# Breakout.net
KiCad netlist of a schematic drawn in EAGLE
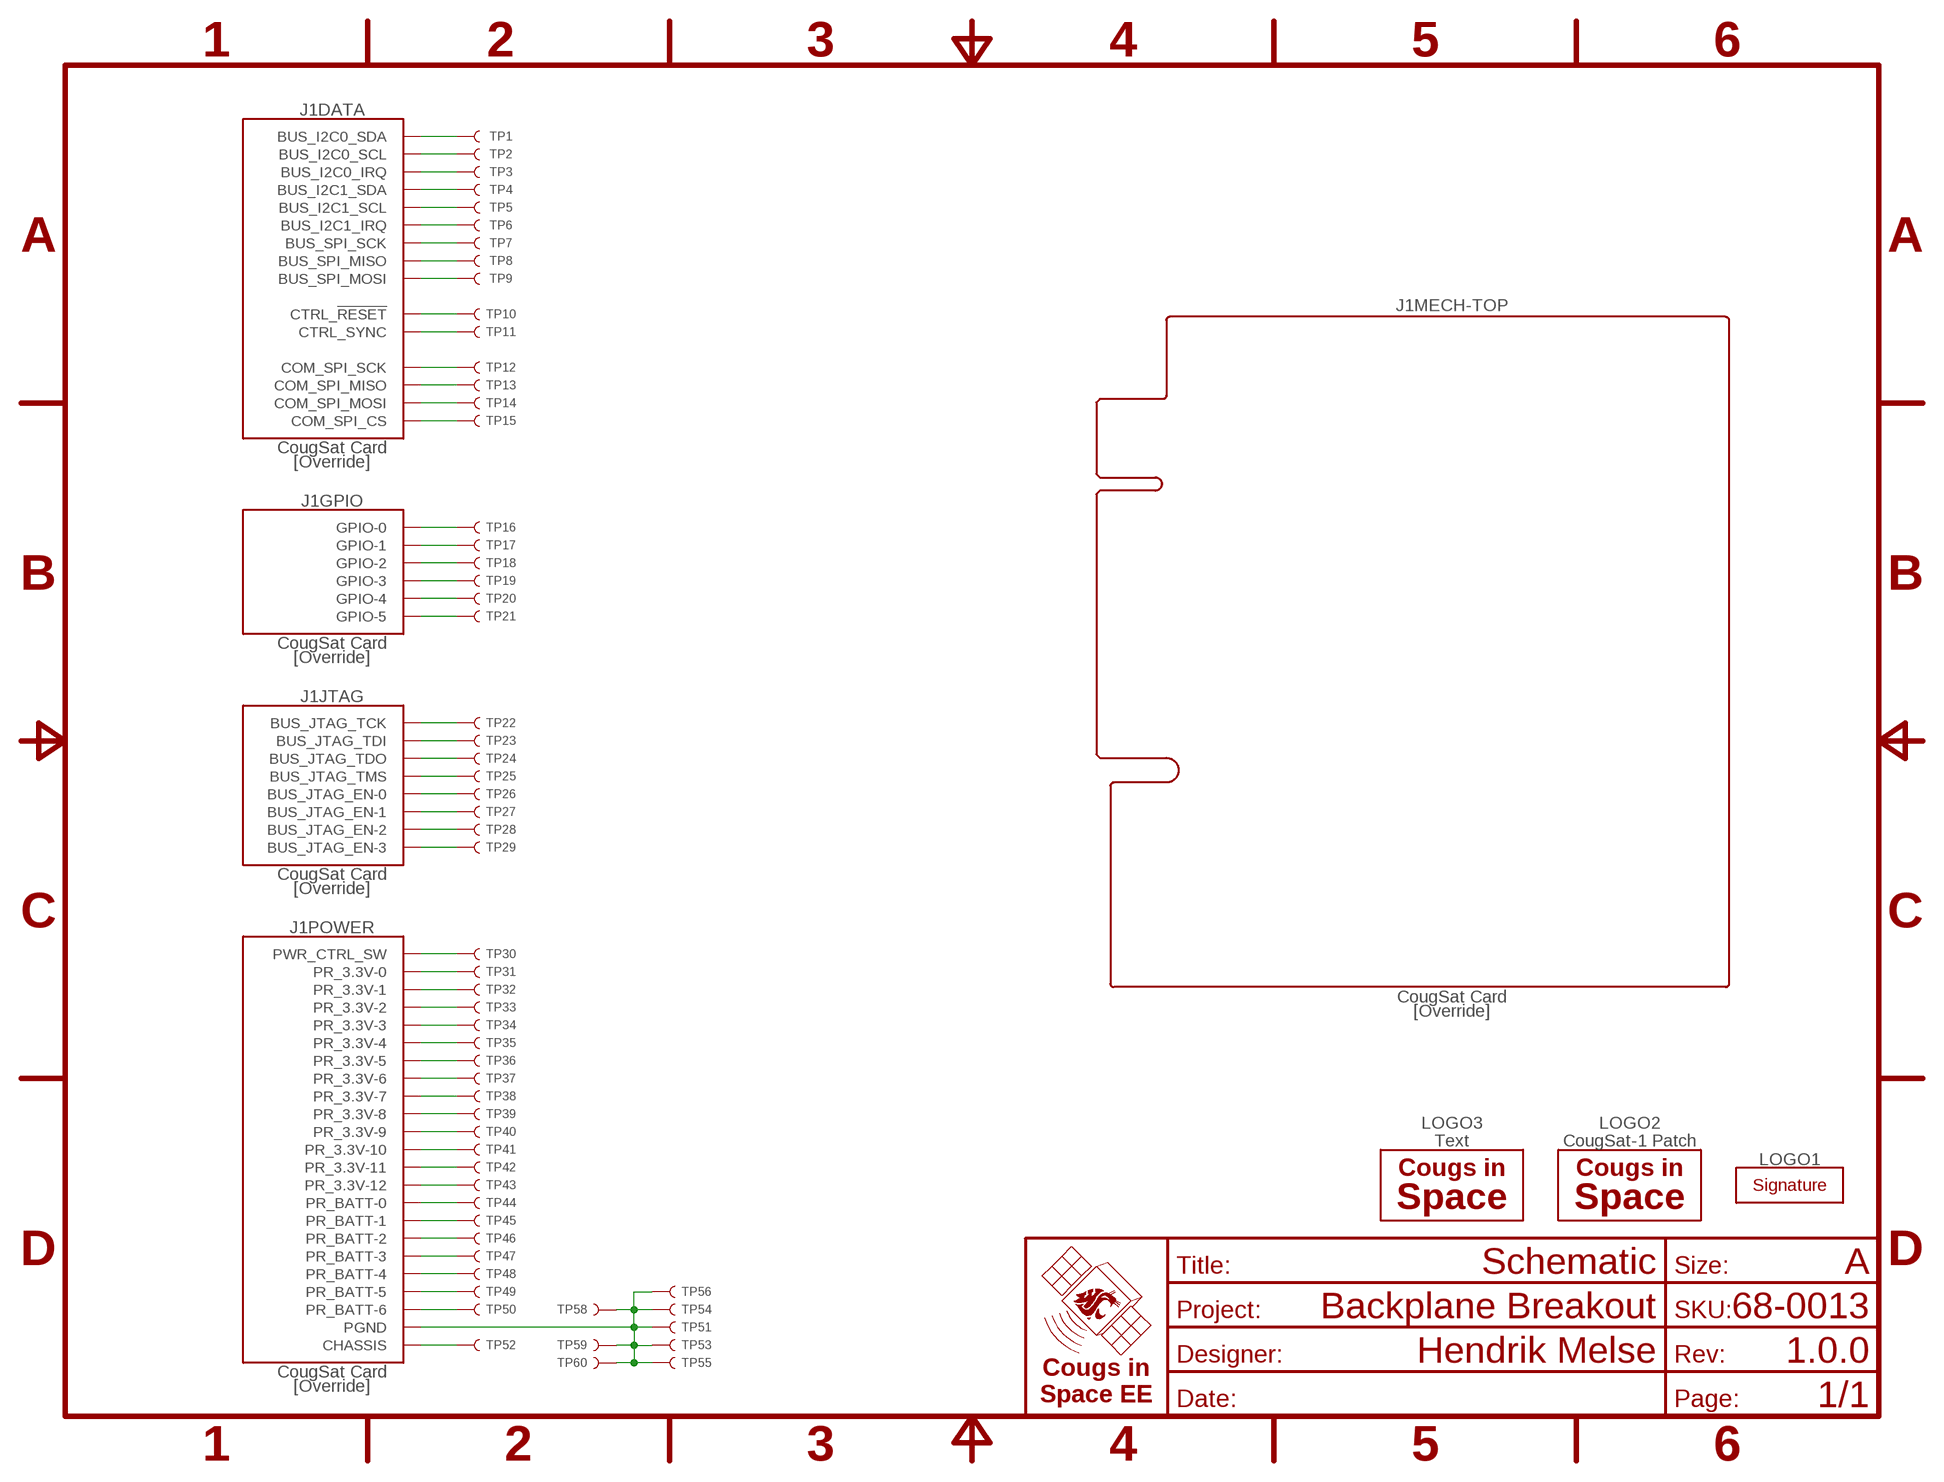
[diagram p0: schematic, sheet 1]

(export (version "E")
  (design (tool "Eeschema 10.0.6"))
  (components
    (comp (ref "J1")
      (value "CougSat Card")
      (footprint "eagle-import:CARD-FULL")
      (libsource (lib "eagle-import") (part "CIS_CARD"))
    )
    (comp (ref "LOGO1")
      (value "SIGNATUREHENDRIK")
      (footprint "eagle-import:SIGN-HENDRIK")
      (libsource (lib "eagle-import") (part "SIGNATUREHENDRIK"))
    )
    (comp (ref "LOGO2")
      (value "CougSat-1 Patch")
      (footprint "eagle-import:CIS-PATCH-1")
      (libsource (lib "eagle-import") (part "CIS-LOGO-PATCH-1"))
    )
    (comp (ref "LOGO3")
      (value "Text")
      (footprint "eagle-import:CIS-TEXT")
      (libsource (lib "eagle-import") (part "CIS-LOGO-TEXT"))
    )
    (comp (ref "TP1")
      (value "TEST_POINT-THT-1.0")
      (footprint "eagle-import:THT-1.0")
      (libsource (lib "eagle-import") (part "TEST_POINT-THT-1.0"))
    )
    (comp (ref "TP2")
      (value "TEST_POINT-THT-1.0")
      (footprint "eagle-import:THT-1.0")
      (libsource (lib "eagle-import") (part "TEST_POINT-THT-1.0"))
    )
    (comp (ref "TP3")
      (value "TEST_POINT-THT-1.0")
      (footprint "eagle-import:THT-1.0")
      (libsource (lib "eagle-import") (part "TEST_POINT-THT-1.0"))
    )
    (comp (ref "TP4")
      (value "TEST_POINT-THT-1.0")
      (footprint "eagle-import:THT-1.0")
      (libsource (lib "eagle-import") (part "TEST_POINT-THT-1.0"))
    )
    (comp (ref "TP5")
      (value "TEST_POINT-THT-1.0")
      (footprint "eagle-import:THT-1.0")
      (libsource (lib "eagle-import") (part "TEST_POINT-THT-1.0"))
    )
    (comp (ref "TP6")
      (value "TEST_POINT-THT-1.0")
      (footprint "eagle-import:THT-1.0")
      (libsource (lib "eagle-import") (part "TEST_POINT-THT-1.0"))
    )
    (comp (ref "TP7")
      (value "TEST_POINT-THT-1.0")
      (footprint "eagle-import:THT-1.0")
      (libsource (lib "eagle-import") (part "TEST_POINT-THT-1.0"))
    )
    (comp (ref "TP8")
      (value "TEST_POINT-THT-1.0")
      (footprint "eagle-import:THT-1.0")
      (libsource (lib "eagle-import") (part "TEST_POINT-THT-1.0"))
    )
    (comp (ref "TP9")
      (value "TEST_POINT-THT-1.0")
      (footprint "eagle-import:THT-1.0")
      (libsource (lib "eagle-import") (part "TEST_POINT-THT-1.0"))
    )
    (comp (ref "TP10")
      (value "TEST_POINT-THT-1.0")
      (footprint "eagle-import:THT-1.0")
      (libsource (lib "eagle-import") (part "TEST_POINT-THT-1.0"))
    )
    (comp (ref "TP11")
      (value "TEST_POINT-THT-1.0")
      (footprint "eagle-import:THT-1.0")
      (libsource (lib "eagle-import") (part "TEST_POINT-THT-1.0"))
    )
    (comp (ref "TP12")
      (value "TEST_POINT-THT-1.0")
      (footprint "eagle-import:THT-1.0")
      (libsource (lib "eagle-import") (part "TEST_POINT-THT-1.0"))
    )
    (comp (ref "TP13")
      (value "TEST_POINT-THT-1.0")
      (footprint "eagle-import:THT-1.0")
      (libsource (lib "eagle-import") (part "TEST_POINT-THT-1.0"))
    )
    (comp (ref "TP14")
      (value "TEST_POINT-THT-1.0")
      (footprint "eagle-import:THT-1.0")
      (libsource (lib "eagle-import") (part "TEST_POINT-THT-1.0"))
    )
    (comp (ref "TP15")
      (value "TEST_POINT-THT-1.0")
      (footprint "eagle-import:THT-1.0")
      (libsource (lib "eagle-import") (part "TEST_POINT-THT-1.0"))
    )
    (comp (ref "TP16")
      (value "TEST_POINT-THT-1.0")
      (footprint "eagle-import:THT-1.0")
      (libsource (lib "eagle-import") (part "TEST_POINT-THT-1.0"))
    )
    (comp (ref "TP17")
      (value "TEST_POINT-THT-1.0")
      (footprint "eagle-import:THT-1.0")
      (libsource (lib "eagle-import") (part "TEST_POINT-THT-1.0"))
    )
    (comp (ref "TP18")
      (value "TEST_POINT-THT-1.0")
      (footprint "eagle-import:THT-1.0")
      (libsource (lib "eagle-import") (part "TEST_POINT-THT-1.0"))
    )
    (comp (ref "TP19")
      (value "TEST_POINT-THT-1.0")
      (footprint "eagle-import:THT-1.0")
      (libsource (lib "eagle-import") (part "TEST_POINT-THT-1.0"))
    )
    (comp (ref "TP20")
      (value "TEST_POINT-THT-1.0")
      (footprint "eagle-import:THT-1.0")
      (libsource (lib "eagle-import") (part "TEST_POINT-THT-1.0"))
    )
    (comp (ref "TP21")
      (value "TEST_POINT-THT-1.0")
      (footprint "eagle-import:THT-1.0")
      (libsource (lib "eagle-import") (part "TEST_POINT-THT-1.0"))
    )
    (comp (ref "TP22")
      (value "TEST_POINT-THT-1.0")
      (footprint "eagle-import:THT-1.0")
      (libsource (lib "eagle-import") (part "TEST_POINT-THT-1.0"))
    )
    (comp (ref "TP23")
      (value "TEST_POINT-THT-1.0")
      (footprint "eagle-import:THT-1.0")
      (libsource (lib "eagle-import") (part "TEST_POINT-THT-1.0"))
    )
    (comp (ref "TP24")
      (value "TEST_POINT-THT-1.0")
      (footprint "eagle-import:THT-1.0")
      (libsource (lib "eagle-import") (part "TEST_POINT-THT-1.0"))
    )
    (comp (ref "TP25")
      (value "TEST_POINT-THT-1.0")
      (footprint "eagle-import:THT-1.0")
      (libsource (lib "eagle-import") (part "TEST_POINT-THT-1.0"))
    )
    (comp (ref "TP26")
      (value "TEST_POINT-THT-1.0")
      (footprint "eagle-import:THT-1.0")
      (libsource (lib "eagle-import") (part "TEST_POINT-THT-1.0"))
    )
    (comp (ref "TP27")
      (value "TEST_POINT-THT-1.0")
      (footprint "eagle-import:THT-1.0")
      (libsource (lib "eagle-import") (part "TEST_POINT-THT-1.0"))
    )
    (comp (ref "TP28")
      (value "TEST_POINT-THT-1.0")
      (footprint "eagle-import:THT-1.0")
      (libsource (lib "eagle-import") (part "TEST_POINT-THT-1.0"))
    )
    (comp (ref "TP29")
      (value "TEST_POINT-THT-1.0")
      (footprint "eagle-import:THT-1.0")
      (libsource (lib "eagle-import") (part "TEST_POINT-THT-1.0"))
    )
    (comp (ref "TP30")
      (value "TEST_POINT-THT-1.0")
      (footprint "eagle-import:THT-1.0")
      (libsource (lib "eagle-import") (part "TEST_POINT-THT-1.0"))
    )
    (comp (ref "TP31")
      (value "TEST_POINT-THT-1.0")
      (footprint "eagle-import:THT-1.0")
      (libsource (lib "eagle-import") (part "TEST_POINT-THT-1.0"))
    )
    (comp (ref "TP32")
      (value "TEST_POINT-THT-1.0")
      (footprint "eagle-import:THT-1.0")
      (libsource (lib "eagle-import") (part "TEST_POINT-THT-1.0"))
    )
    (comp (ref "TP33")
      (value "TEST_POINT-THT-1.0")
      (footprint "eagle-import:THT-1.0")
      (libsource (lib "eagle-import") (part "TEST_POINT-THT-1.0"))
    )
    (comp (ref "TP34")
      (value "TEST_POINT-THT-1.0")
      (footprint "eagle-import:THT-1.0")
      (libsource (lib "eagle-import") (part "TEST_POINT-THT-1.0"))
    )
    (comp (ref "TP35")
      (value "TEST_POINT-THT-1.0")
      (footprint "eagle-import:THT-1.0")
      (libsource (lib "eagle-import") (part "TEST_POINT-THT-1.0"))
    )
    (comp (ref "TP36")
      (value "TEST_POINT-THT-1.0")
      (footprint "eagle-import:THT-1.0")
      (libsource (lib "eagle-import") (part "TEST_POINT-THT-1.0"))
    )
    (comp (ref "TP37")
      (value "TEST_POINT-THT-1.0")
      (footprint "eagle-import:THT-1.0")
      (libsource (lib "eagle-import") (part "TEST_POINT-THT-1.0"))
    )
    (comp (ref "TP38")
      (value "TEST_POINT-THT-1.0")
      (footprint "eagle-import:THT-1.0")
      (libsource (lib "eagle-import") (part "TEST_POINT-THT-1.0"))
    )
    (comp (ref "TP39")
      (value "TEST_POINT-THT-1.0")
      (footprint "eagle-import:THT-1.0")
      (libsource (lib "eagle-import") (part "TEST_POINT-THT-1.0"))
    )
    (comp (ref "TP40")
      (value "TEST_POINT-THT-1.0")
      (footprint "eagle-import:THT-1.0")
      (libsource (lib "eagle-import") (part "TEST_POINT-THT-1.0"))
    )
    (comp (ref "TP41")
      (value "TEST_POINT-THT-1.0")
      (footprint "eagle-import:THT-1.0")
      (libsource (lib "eagle-import") (part "TEST_POINT-THT-1.0"))
    )
    (comp (ref "TP42")
      (value "TEST_POINT-THT-1.0")
      (footprint "eagle-import:THT-1.0")
      (libsource (lib "eagle-import") (part "TEST_POINT-THT-1.0"))
    )
    (comp (ref "TP43")
      (value "TEST_POINT-THT-1.0")
      (footprint "eagle-import:THT-1.0")
      (libsource (lib "eagle-import") (part "TEST_POINT-THT-1.0"))
    )
    (comp (ref "TP44")
      (value "TEST_POINT-THT-1.0")
      (footprint "eagle-import:THT-1.0")
      (libsource (lib "eagle-import") (part "TEST_POINT-THT-1.0"))
    )
    (comp (ref "TP45")
      (value "TEST_POINT-THT-1.0")
      (footprint "eagle-import:THT-1.0")
      (libsource (lib "eagle-import") (part "TEST_POINT-THT-1.0"))
    )
    (comp (ref "TP46")
      (value "TEST_POINT-THT-1.0")
      (footprint "eagle-import:THT-1.0")
      (libsource (lib "eagle-import") (part "TEST_POINT-THT-1.0"))
    )
    (comp (ref "TP47")
      (value "TEST_POINT-THT-1.0")
      (footprint "eagle-import:THT-1.0")
      (libsource (lib "eagle-import") (part "TEST_POINT-THT-1.0"))
    )
    (comp (ref "TP48")
      (value "TEST_POINT-THT-1.0")
      (footprint "eagle-import:THT-1.0")
      (libsource (lib "eagle-import") (part "TEST_POINT-THT-1.0"))
    )
    (comp (ref "TP49")
      (value "TEST_POINT-THT-1.0")
      (footprint "eagle-import:THT-1.0")
      (libsource (lib "eagle-import") (part "TEST_POINT-THT-1.0"))
    )
    (comp (ref "TP50")
      (value "TEST_POINT-THT-1.0")
      (footprint "eagle-import:THT-1.0")
      (libsource (lib "eagle-import") (part "TEST_POINT-THT-1.0"))
    )
    (comp (ref "TP51")
      (value "TEST_POINT-THT-1.0")
      (footprint "eagle-import:THT-1.0")
      (libsource (lib "eagle-import") (part "TEST_POINT-THT-1.0"))
    )
    (comp (ref "TP52")
      (value "TEST_POINT-THT-1.0")
      (footprint "eagle-import:THT-1.0")
      (libsource (lib "eagle-import") (part "TEST_POINT-THT-1.0"))
    )
    (comp (ref "TP53")
      (value "TEST_POINT-THT-1.0")
      (footprint "eagle-import:THT-1.0")
      (libsource (lib "eagle-import") (part "TEST_POINT-THT-1.0"))
    )
    (comp (ref "TP54")
      (value "TEST_POINT-THT-1.0")
      (footprint "eagle-import:THT-1.0")
      (libsource (lib "eagle-import") (part "TEST_POINT-THT-1.0"))
    )
    (comp (ref "TP55")
      (value "TEST_POINT-THT-1.0")
      (footprint "eagle-import:THT-1.0")
      (libsource (lib "eagle-import") (part "TEST_POINT-THT-1.0"))
    )
    (comp (ref "TP56")
      (value "TEST_POINT-THT-1.0")
      (footprint "eagle-import:THT-1.0")
      (libsource (lib "eagle-import") (part "TEST_POINT-THT-1.0"))
    )
    (comp (ref "TP58")
      (value "TEST_POINT-THT-1.0")
      (footprint "eagle-import:THT-1.0")
      (libsource (lib "eagle-import") (part "TEST_POINT-THT-1.0"))
    )
    (comp (ref "TP59")
      (value "TEST_POINT-THT-1.0")
      (footprint "eagle-import:THT-1.0")
      (libsource (lib "eagle-import") (part "TEST_POINT-THT-1.0"))
    )
    (comp (ref "TP60")
      (value "TEST_POINT-THT-1.0")
      (footprint "eagle-import:THT-1.0")
      (libsource (lib "eagle-import") (part "TEST_POINT-THT-1.0"))
    )
  )
  (nets
    (net (code "1") (name "/CHASSIS") (class "Default")
      (node (ref "J1") (pin "CHASSIS@1") (pinfunction "CHASSIS_CHASSIS@1") (pintype "power_in"))
      (node (ref "J1") (pin "CHASSIS@2") (pinfunction "CHASSIS_CHASSIS@2") (pintype "power_in"))
      (node (ref "J1") (pin "CHASSIS@3") (pinfunction "CHASSIS_CHASSIS@3") (pintype "power_in"))
      (node (ref "J1") (pin "CHASSIS@4") (pinfunction "CHASSIS_CHASSIS@4") (pintype "power_in"))
      (node (ref "TP52") (pin "1") (pinfunction "1_1") (pintype "passive"))
    )
    (net (code "2") (name "/PGND") (class "Default")
      (node (ref "J1") (pin "A21") (pinfunction "PGND_A21") (pintype "power_in"))
      (node (ref "J1") (pin "A22") (pinfunction "PGND_A22") (pintype "power_in"))
      (node (ref "J1") (pin "A23") (pinfunction "PGND_A23") (pintype "power_in"))
      (node (ref "J1") (pin "B21") (pinfunction "PGND_B21") (pintype "power_in"))
      (node (ref "J1") (pin "B22") (pinfunction "PGND_B22") (pintype "power_in"))
      (node (ref "J1") (pin "B23") (pinfunction "PGND_B23") (pintype "power_in"))
      (node (ref "J1") (pin "B24") (pinfunction "PGND_B24") (pintype "power_in"))
      (node (ref "J1") (pin "B25") (pinfunction "PGND_B25") (pintype "power_in"))
      (node (ref "J1") (pin "B26") (pinfunction "PGND_B26") (pintype "power_in"))
      (node (ref "J1") (pin "B27") (pinfunction "PGND_B27") (pintype "power_in"))
      (node (ref "J1") (pin "B28") (pinfunction "PGND_B28") (pintype "power_in"))
      (node (ref "J1") (pin "B29") (pinfunction "PGND_B29") (pintype "power_in"))
      (node (ref "TP51") (pin "1") (pinfunction "1_1") (pintype "passive"))
      (node (ref "TP53") (pin "1") (pinfunction "1_1") (pintype "passive"))
      (node (ref "TP54") (pin "1") (pinfunction "1_1") (pintype "passive"))
      (node (ref "TP55") (pin "1") (pinfunction "1_1") (pintype "passive"))
      (node (ref "TP56") (pin "1") (pinfunction "1_1") (pintype "passive"))
      (node (ref "TP58") (pin "1") (pinfunction "1_1") (pintype "passive"))
      (node (ref "TP59") (pin "1") (pinfunction "1_1") (pintype "passive"))
      (node (ref "TP60") (pin "1") (pinfunction "1_1") (pintype "passive"))
    )
    (net (code "3") (name "/PR_3.3V-0") (class "Default")
      (node (ref "J1") (pin "A1") (pinfunction "PR_3.3V-0_A1") (pintype "power_in"))
      (node (ref "J1") (pin "B1") (pinfunction "PR_3.3V-0_B1") (pintype "power_in"))
      (node (ref "TP31") (pin "1") (pinfunction "1_1") (pintype "passive"))
    )
    (net (code "4") (name "/PR_3.3V-1") (class "Default")
      (node (ref "J1") (pin "A2") (pinfunction "PR_3.3V-1_A2") (pintype "power_in"))
      (node (ref "J1") (pin "B2") (pinfunction "PR_3.3V-1_B2") (pintype "power_in"))
      (node (ref "TP32") (pin "1") (pinfunction "1_1") (pintype "passive"))
    )
    (net (code "5") (name "/PR_3.3V-2") (class "Default")
      (node (ref "J1") (pin "A3") (pinfunction "PR_3.3V-2_A3") (pintype "power_in"))
      (node (ref "J1") (pin "B3") (pinfunction "PR_3.3V-2_B3") (pintype "power_in"))
      (node (ref "TP33") (pin "1") (pinfunction "1_1") (pintype "passive"))
    )
    (net (code "6") (name "/PR_3.3V-3") (class "Default")
      (node (ref "J1") (pin "A4") (pinfunction "PR_3.3V-3_A4") (pintype "power_in"))
      (node (ref "J1") (pin "B4") (pinfunction "PR_3.3V-3_B4") (pintype "power_in"))
      (node (ref "TP34") (pin "1") (pinfunction "1_1") (pintype "passive"))
    )
    (net (code "7") (name "/PR_3.3V-4") (class "Default")
      (node (ref "J1") (pin "A5") (pinfunction "PR_3.3V-4_A5") (pintype "power_in"))
      (node (ref "J1") (pin "B5") (pinfunction "PR_3.3V-4_B5") (pintype "power_in"))
      (node (ref "TP35") (pin "1") (pinfunction "1_1") (pintype "passive"))
    )
    (net (code "8") (name "/PR_3.3V-5") (class "Default")
      (node (ref "J1") (pin "A6") (pinfunction "PR_3.3V-5_A6") (pintype "power_in"))
      (node (ref "J1") (pin "B6") (pinfunction "PR_3.3V-5_B6") (pintype "power_in"))
      (node (ref "TP36") (pin "1") (pinfunction "1_1") (pintype "passive"))
    )
    (net (code "9") (name "/PR_3.3V-6") (class "Default")
      (node (ref "J1") (pin "A7") (pinfunction "PR_3.3V-6_A7") (pintype "power_in"))
      (node (ref "J1") (pin "B7") (pinfunction "PR_3.3V-6_B7") (pintype "power_in"))
      (node (ref "TP37") (pin "1") (pinfunction "1_1") (pintype "passive"))
    )
    (net (code "10") (name "/PR_3.3V-7") (class "Default")
      (node (ref "J1") (pin "A8") (pinfunction "PR_3.3V-7_A8") (pintype "power_in"))
      (node (ref "J1") (pin "B8") (pinfunction "PR_3.3V-7_B8") (pintype "power_in"))
      (node (ref "TP38") (pin "1") (pinfunction "1_1") (pintype "passive"))
    )
    (net (code "11") (name "/PR_3.3V-8") (class "Default")
      (node (ref "J1") (pin "A9") (pinfunction "PR_3.3V-8_A9") (pintype "power_in"))
      (node (ref "J1") (pin "B9") (pinfunction "PR_3.3V-8_B9") (pintype "power_in"))
      (node (ref "TP39") (pin "1") (pinfunction "1_1") (pintype "passive"))
    )
    (net (code "12") (name "/PR_3.3V-9") (class "Default")
      (node (ref "J1") (pin "A10") (pinfunction "PR_3.3V-9_A10") (pintype "power_in"))
      (node (ref "J1") (pin "B10") (pinfunction "PR_3.3V-9_B10") (pintype "power_in"))
      (node (ref "TP40") (pin "1") (pinfunction "1_1") (pintype "passive"))
    )
    (net (code "13") (name "/PR_3.3V-10") (class "Default")
      (node (ref "J1") (pin "A11") (pinfunction "PR_3.3V-10_A11") (pintype "power_in"))
      (node (ref "J1") (pin "B11") (pinfunction "PR_3.3V-10_B11") (pintype "power_in"))
      (node (ref "TP41") (pin "1") (pinfunction "1_1") (pintype "passive"))
    )
    (net (code "14") (name "/PR_3.3V-11") (class "Default")
      (node (ref "J1") (pin "A12") (pinfunction "PR_3.3V-11_A12") (pintype "power_in"))
      (node (ref "J1") (pin "B12") (pinfunction "PR_3.3V-11_B12") (pintype "power_in"))
      (node (ref "TP42") (pin "1") (pinfunction "1_1") (pintype "passive"))
    )
    (net (code "15") (name "/PR_3.3V-12") (class "Default")
      (node (ref "J1") (pin "A13") (pinfunction "PR_3.3V-12_A13") (pintype "power_in"))
      (node (ref "J1") (pin "B13") (pinfunction "PR_3.3V-12_B13") (pintype "power_in"))
      (node (ref "TP43") (pin "1") (pinfunction "1_1") (pintype "passive"))
    )
    (net (code "16") (name "/PR_BATT-0") (class "Default")
      (node (ref "J1") (pin "A14") (pinfunction "PR_BATT-0_A14") (pintype "power_in"))
      (node (ref "J1") (pin "B14") (pinfunction "PR_BATT-0_B14") (pintype "power_in"))
      (node (ref "TP44") (pin "1") (pinfunction "1_1") (pintype "passive"))
    )
    (net (code "17") (name "/PR_BATT-1") (class "Default")
      (node (ref "J1") (pin "A15") (pinfunction "PR_BATT-1_A15") (pintype "power_in"))
      (node (ref "J1") (pin "B15") (pinfunction "PR_BATT-1_B15") (pintype "power_in"))
      (node (ref "TP45") (pin "1") (pinfunction "1_1") (pintype "passive"))
    )
    (net (code "18") (name "/PR_BATT-2") (class "Default")
      (node (ref "J1") (pin "A16") (pinfunction "PR_BATT-2_A16") (pintype "power_in"))
      (node (ref "J1") (pin "B16") (pinfunction "PR_BATT-2_B16") (pintype "power_in"))
      (node (ref "TP46") (pin "1") (pinfunction "1_1") (pintype "passive"))
    )
    (net (code "19") (name "/PR_BATT-3") (class "Default")
      (node (ref "J1") (pin "A17") (pinfunction "PR_BATT-3_A17") (pintype "power_in"))
      (node (ref "J1") (pin "B17") (pinfunction "PR_BATT-3_B17") (pintype "power_in"))
      (node (ref "TP47") (pin "1") (pinfunction "1_1") (pintype "passive"))
    )
    (net (code "20") (name "/PR_BATT-4") (class "Default")
      (node (ref "J1") (pin "A18") (pinfunction "PR_BATT-4_A18") (pintype "power_in"))
      (node (ref "J1") (pin "B18") (pinfunction "PR_BATT-4_B18") (pintype "power_in"))
      (node (ref "TP48") (pin "1") (pinfunction "1_1") (pintype "passive"))
    )
    (net (code "21") (name "/PR_BATT-5") (class "Default")
      (node (ref "J1") (pin "A19") (pinfunction "PR_BATT-5_A19") (pintype "power_in"))
      (node (ref "J1") (pin "B19") (pinfunction "PR_BATT-5_B19") (pintype "power_in"))
      (node (ref "TP49") (pin "1") (pinfunction "1_1") (pintype "passive"))
    )
    (net (code "22") (name "/PR_BATT-6") (class "Default")
      (node (ref "J1") (pin "A20") (pinfunction "PR_BATT-6_A20") (pintype "power_in"))
      (node (ref "J1") (pin "B20") (pinfunction "PR_BATT-6_B20") (pintype "power_in"))
      (node (ref "TP50") (pin "1") (pinfunction "1_1") (pintype "passive"))
    )
    (net (code "23") (name "Net-(J1A-BUS_I2C0_IRQ-PadA45)") (class "Default")
      (node (ref "J1") (pin "A45") (pinfunction "BUS_I2C0_IRQ_A45") (pintype "bidirectional"))
      (node (ref "J1") (pin "B45") (pinfunction "BUS_I2C0_IRQ_B45") (pintype "bidirectional"))
      (node (ref "TP3") (pin "1") (pinfunction "1_1") (pintype "passive"))
    )
    (net (code "24") (name "Net-(J1A-BUS_I2C0_SCL-PadA44)") (class "Default")
      (node (ref "J1") (pin "A44") (pinfunction "BUS_I2C0_SCL_A44") (pintype "bidirectional"))
      (node (ref "J1") (pin "B44") (pinfunction "BUS_I2C0_SCL_B44") (pintype "bidirectional"))
      (node (ref "TP2") (pin "1") (pinfunction "1_1") (pintype "passive"))
    )
    (net (code "25") (name "Net-(J1A-BUS_I2C0_SDA-PadA43)") (class "Default")
      (node (ref "J1") (pin "A43") (pinfunction "BUS_I2C0_SDA_A43") (pintype "bidirectional"))
      (node (ref "J1") (pin "B43") (pinfunction "BUS_I2C0_SDA_B43") (pintype "bidirectional"))
      (node (ref "TP1") (pin "1") (pinfunction "1_1") (pintype "passive"))
    )
    (net (code "26") (name "Net-(J1A-BUS_I2C1_IRQ-PadA32)") (class "Default")
      (node (ref "J1") (pin "A32") (pinfunction "BUS_I2C1_IRQ_A32") (pintype "bidirectional"))
      (node (ref "J1") (pin "B32") (pinfunction "BUS_I2C1_IRQ_B32") (pintype "bidirectional"))
      (node (ref "TP6") (pin "1") (pinfunction "1_1") (pintype "passive"))
    )
    (net (code "27") (name "Net-(J1A-BUS_I2C1_SCL-PadA31)") (class "Default")
      (node (ref "J1") (pin "A31") (pinfunction "BUS_I2C1_SCL_A31") (pintype "bidirectional"))
      (node (ref "J1") (pin "B31") (pinfunction "BUS_I2C1_SCL_B31") (pintype "bidirectional"))
      (node (ref "TP5") (pin "1") (pinfunction "1_1") (pintype "passive"))
    )
    (net (code "28") (name "Net-(J1A-BUS_I2C1_SDA-PadA30)") (class "Default")
      (node (ref "J1") (pin "A30") (pinfunction "BUS_I2C1_SDA_A30") (pintype "bidirectional"))
      (node (ref "J1") (pin "B30") (pinfunction "BUS_I2C1_SDA_B30") (pintype "bidirectional"))
      (node (ref "TP4") (pin "1") (pinfunction "1_1") (pintype "passive"))
    )
    (net (code "29") (name "Net-(J1A-BUS_SPI_MISO-PadA38)") (class "Default")
      (node (ref "J1") (pin "A38") (pinfunction "BUS_SPI_MISO_A38") (pintype "bidirectional"))
      (node (ref "J1") (pin "B38") (pinfunction "BUS_SPI_MISO_B38") (pintype "bidirectional"))
      (node (ref "TP8") (pin "1") (pinfunction "1_1") (pintype "passive"))
    )
    (net (code "30") (name "Net-(J1A-BUS_SPI_MOSI-PadA39)") (class "Default")
      (node (ref "J1") (pin "A39") (pinfunction "BUS_SPI_MOSI_A39") (pintype "bidirectional"))
      (node (ref "J1") (pin "B39") (pinfunction "BUS_SPI_MOSI_B39") (pintype "bidirectional"))
      (node (ref "TP9") (pin "1") (pinfunction "1_1") (pintype "passive"))
    )
    (net (code "31") (name "Net-(J1A-BUS_SPI_SCK-PadA37)") (class "Default")
      (node (ref "J1") (pin "A37") (pinfunction "BUS_SPI_SCK_A37") (pintype "bidirectional"))
      (node (ref "J1") (pin "B37") (pinfunction "BUS_SPI_SCK_B37") (pintype "bidirectional"))
      (node (ref "TP7") (pin "1") (pinfunction "1_1") (pintype "passive"))
    )
    (net (code "32") (name "Net-(J1A-COM_SPI_CS-PadA36)") (class "Default")
      (node (ref "J1") (pin "A36") (pinfunction "COM_SPI_CS_A36") (pintype "bidirectional"))
      (node (ref "J1") (pin "B36") (pinfunction "COM_SPI_CS_B36") (pintype "bidirectional"))
      (node (ref "TP15") (pin "1") (pinfunction "1_1") (pintype "passive"))
    )
    (net (code "33") (name "Net-(J1A-COM_SPI_MISO-PadA34)") (class "Default")
      (node (ref "J1") (pin "A34") (pinfunction "COM_SPI_MISO_A34") (pintype "bidirectional"))
      (node (ref "J1") (pin "B34") (pinfunction "COM_SPI_MISO_B34") (pintype "bidirectional"))
      (node (ref "TP13") (pin "1") (pinfunction "1_1") (pintype "passive"))
    )
    (net (code "34") (name "Net-(J1A-COM_SPI_MOSI-PadA35)") (class "Default")
      (node (ref "J1") (pin "A35") (pinfunction "COM_SPI_MOSI_A35") (pintype "bidirectional"))
      (node (ref "J1") (pin "B35") (pinfunction "COM_SPI_MOSI_B35") (pintype "bidirectional"))
      (node (ref "TP14") (pin "1") (pinfunction "1_1") (pintype "passive"))
    )
    (net (code "35") (name "Net-(J1A-COM_SPI_SCK-PadA33)") (class "Default")
      (node (ref "J1") (pin "A33") (pinfunction "COM_SPI_SCK_A33") (pintype "bidirectional"))
      (node (ref "J1") (pin "B33") (pinfunction "COM_SPI_SCK_B33") (pintype "bidirectional"))
      (node (ref "TP12") (pin "1") (pinfunction "1_1") (pintype "passive"))
    )
    (net (code "36") (name "Net-(J1A-CTRL_SYNC-PadA42)") (class "Default")
      (node (ref "J1") (pin "A42") (pinfunction "CTRL_SYNC_A42") (pintype "bidirectional"))
      (node (ref "J1") (pin "B42") (pinfunction "CTRL_SYNC_B42") (pintype "bidirectional"))
      (node (ref "TP11") (pin "1") (pinfunction "1_1") (pintype "passive"))
    )
    (net (code "37") (name "Net-(J1A-CTRL_~{RESET}-PadA41)") (class "Default")
      (node (ref "J1") (pin "A41") (pinfunction "CTRL_~{RESET}_A41") (pintype "bidirectional"))
      (node (ref "J1") (pin "B41") (pinfunction "CTRL_~{RESET}_B41") (pintype "bidirectional"))
      (node (ref "TP10") (pin "1") (pinfunction "1_1") (pintype "passive"))
    )
    (net (code "38") (name "Net-(J1B-GPIO-0)") (class "Default")
      (node (ref "J1") (pin "A24") (pinfunction "GPIO-0_A24") (pintype "bidirectional"))
      (node (ref "TP16") (pin "1") (pinfunction "1_1") (pintype "passive"))
    )
    (net (code "39") (name "Net-(J1B-GPIO-1)") (class "Default")
      (node (ref "J1") (pin "A25") (pinfunction "GPIO-1_A25") (pintype "bidirectional"))
      (node (ref "TP17") (pin "1") (pinfunction "1_1") (pintype "passive"))
    )
    (net (code "40") (name "Net-(J1B-GPIO-2)") (class "Default")
      (node (ref "J1") (pin "A26") (pinfunction "GPIO-2_A26") (pintype "bidirectional"))
      (node (ref "TP18") (pin "1") (pinfunction "1_1") (pintype "passive"))
    )
    (net (code "41") (name "Net-(J1B-GPIO-3)") (class "Default")
      (node (ref "J1") (pin "A27") (pinfunction "GPIO-3_A27") (pintype "bidirectional"))
      (node (ref "TP19") (pin "1") (pinfunction "1_1") (pintype "passive"))
    )
    (net (code "42") (name "Net-(J1B-GPIO-4)") (class "Default")
      (node (ref "J1") (pin "A28") (pinfunction "GPIO-4_A28") (pintype "bidirectional"))
      (node (ref "TP20") (pin "1") (pinfunction "1_1") (pintype "passive"))
    )
    (net (code "43") (name "Net-(J1B-GPIO-5)") (class "Default")
      (node (ref "J1") (pin "A29") (pinfunction "GPIO-5_A29") (pintype "bidirectional"))
      (node (ref "TP21") (pin "1") (pinfunction "1_1") (pintype "passive"))
    )
    (net (code "44") (name "Net-(J1C-BUS_JTAG_EN-0)") (class "Default")
      (node (ref "J1") (pin "B46") (pinfunction "BUS_JTAG_EN-0_B46") (pintype "bidirectional"))
      (node (ref "TP26") (pin "1") (pinfunction "1_1") (pintype "passive"))
    )
    (net (code "45") (name "Net-(J1C-BUS_JTAG_EN-1)") (class "Default")
      (node (ref "J1") (pin "B47") (pinfunction "BUS_JTAG_EN-1_B47") (pintype "bidirectional"))
      (node (ref "TP27") (pin "1") (pinfunction "1_1") (pintype "passive"))
    )
    (net (code "46") (name "Net-(J1C-BUS_JTAG_EN-2)") (class "Default")
      (node (ref "J1") (pin "B48") (pinfunction "BUS_JTAG_EN-2_B48") (pintype "bidirectional"))
      (node (ref "TP28") (pin "1") (pinfunction "1_1") (pintype "passive"))
    )
    (net (code "47") (name "Net-(J1C-BUS_JTAG_EN-3)") (class "Default")
      (node (ref "J1") (pin "B49") (pinfunction "BUS_JTAG_EN-3_B49") (pintype "bidirectional"))
      (node (ref "TP29") (pin "1") (pinfunction "1_1") (pintype "passive"))
    )
    (net (code "48") (name "Net-(J1C-BUS_JTAG_TCK)") (class "Default")
      (node (ref "J1") (pin "A46") (pinfunction "BUS_JTAG_TCK_A46") (pintype "bidirectional"))
      (node (ref "TP22") (pin "1") (pinfunction "1_1") (pintype "passive"))
    )
    (net (code "49") (name "Net-(J1C-BUS_JTAG_TDI)") (class "Default")
      (node (ref "J1") (pin "A47") (pinfunction "BUS_JTAG_TDI_A47") (pintype "bidirectional"))
      (node (ref "TP23") (pin "1") (pinfunction "1_1") (pintype "passive"))
    )
    (net (code "50") (name "Net-(J1C-BUS_JTAG_TDO)") (class "Default")
      (node (ref "J1") (pin "A48") (pinfunction "BUS_JTAG_TDO_A48") (pintype "bidirectional"))
      (node (ref "TP24") (pin "1") (pinfunction "1_1") (pintype "passive"))
    )
    (net (code "51") (name "Net-(J1C-BUS_JTAG_TMS)") (class "Default")
      (node (ref "J1") (pin "A49") (pinfunction "BUS_JTAG_TMS_A49") (pintype "bidirectional"))
      (node (ref "TP25") (pin "1") (pinfunction "1_1") (pintype "passive"))
    )
    (net (code "52") (name "Net-(J1F-PWR_CTRL_SW-PadA40)") (class "Default")
      (node (ref "J1") (pin "A40") (pinfunction "PWR_CTRL_SW_A40") (pintype "bidirectional"))
      (node (ref "J1") (pin "B40") (pinfunction "PWR_CTRL_SW_B40") (pintype "bidirectional"))
      (node (ref "TP30") (pin "1") (pinfunction "1_1") (pintype "passive"))
    )
  )
)
